# Rev1.net
KiCad netlist of a schematic drawn in EAGLE
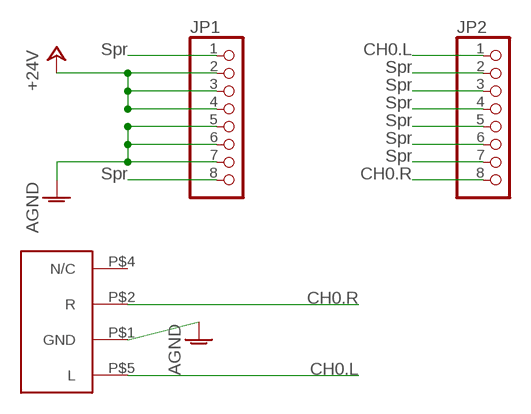
[diagram p0: schematic, sheet 1]

(export (version "E")
  (design (tool "Eeschema 10.0.6"))
  (components
    (comp (ref "JP1")
      (value "PINHD-1X8")
      (footprint "eagle-import:1X08")
      (libsource (lib "eagle-import") (part "PINHD-1X8"))
    )
    (comp (ref "JP2")
      (value "PINHD-1X8")
      (footprint "eagle-import:1X08")
      (libsource (lib "eagle-import") (part "PINHD-1X8"))
    )
    (comp (ref "U$1")
      (value "161-3509-E")
      (footprint "eagle-import:161-3509-E")
      (libsource (lib "eagle-import") (part "161-3509-E"))
    )
  )
  (nets
    (net (code "1") (name "+24V") (class "Default")
      (node (ref "JP1") (pin "2") (pinfunction "2_2") (pintype "passive"))
      (node (ref "JP1") (pin "3") (pinfunction "3_3") (pintype "passive"))
      (node (ref "JP1") (pin "4") (pinfunction "4_4") (pintype "passive"))
    )
    (net (code "2") (name "/CH0.L") (class "Default")
      (node (ref "JP2") (pin "1") (pinfunction "1_1") (pintype "passive"))
      (node (ref "U$1") (pin "P$5") (pinfunction "L_P$5") (pintype "bidirectional"))
    )
    (net (code "3") (name "/CH0.R") (class "Default")
      (node (ref "JP2") (pin "8") (pinfunction "8_8") (pintype "passive"))
      (node (ref "U$1") (pin "P$2") (pinfunction "R_P$2") (pintype "bidirectional"))
    )
    (net (code "4") (name "AGND") (class "Default")
      (node (ref "JP1") (pin "5") (pinfunction "5_5") (pintype "passive"))
      (node (ref "JP1") (pin "6") (pinfunction "6_6") (pintype "passive"))
      (node (ref "JP1") (pin "7") (pinfunction "7_7") (pintype "passive"))
      (node (ref "U$1") (pin "P$1") (pinfunction "GND_P$1") (pintype "bidirectional"))
    )
    (net (code "5") (name "unconnected-(JP1-Pad1)") (class "Default")
      (node (ref "JP1") (pin "1") (pinfunction "1_1") (pintype "passive"))
    )
    (net (code "6") (name "unconnected-(JP1-Pad8)") (class "Default")
      (node (ref "JP1") (pin "8") (pinfunction "8_8") (pintype "passive"))
    )
    (net (code "7") (name "unconnected-(JP2-Pad2)") (class "Default")
      (node (ref "JP2") (pin "2") (pinfunction "2_2") (pintype "passive"))
    )
    (net (code "8") (name "unconnected-(JP2-Pad3)") (class "Default")
      (node (ref "JP2") (pin "3") (pinfunction "3_3") (pintype "passive"))
    )
    (net (code "9") (name "unconnected-(JP2-Pad4)") (class "Default")
      (node (ref "JP2") (pin "4") (pinfunction "4_4") (pintype "passive"))
    )
    (net (code "10") (name "unconnected-(JP2-Pad5)") (class "Default")
      (node (ref "JP2") (pin "5") (pinfunction "5_5") (pintype "passive"))
    )
    (net (code "11") (name "unconnected-(JP2-Pad6)") (class "Default")
      (node (ref "JP2") (pin "6") (pinfunction "6_6") (pintype "passive"))
    )
    (net (code "12") (name "unconnected-(JP2-Pad7)") (class "Default")
      (node (ref "JP2") (pin "7") (pinfunction "7_7") (pintype "passive"))
    )
    (net (code "13") (name "unconnected-(U$1-N{slash}C-PadP$4)") (class "Default")
      (node (ref "U$1") (pin "P$4") (pinfunction "N/C_P$4") (pintype "bidirectional"))
    )
  )
)
